# ASCII.net
KiCad netlist of a schematic drawn in Altium Designer
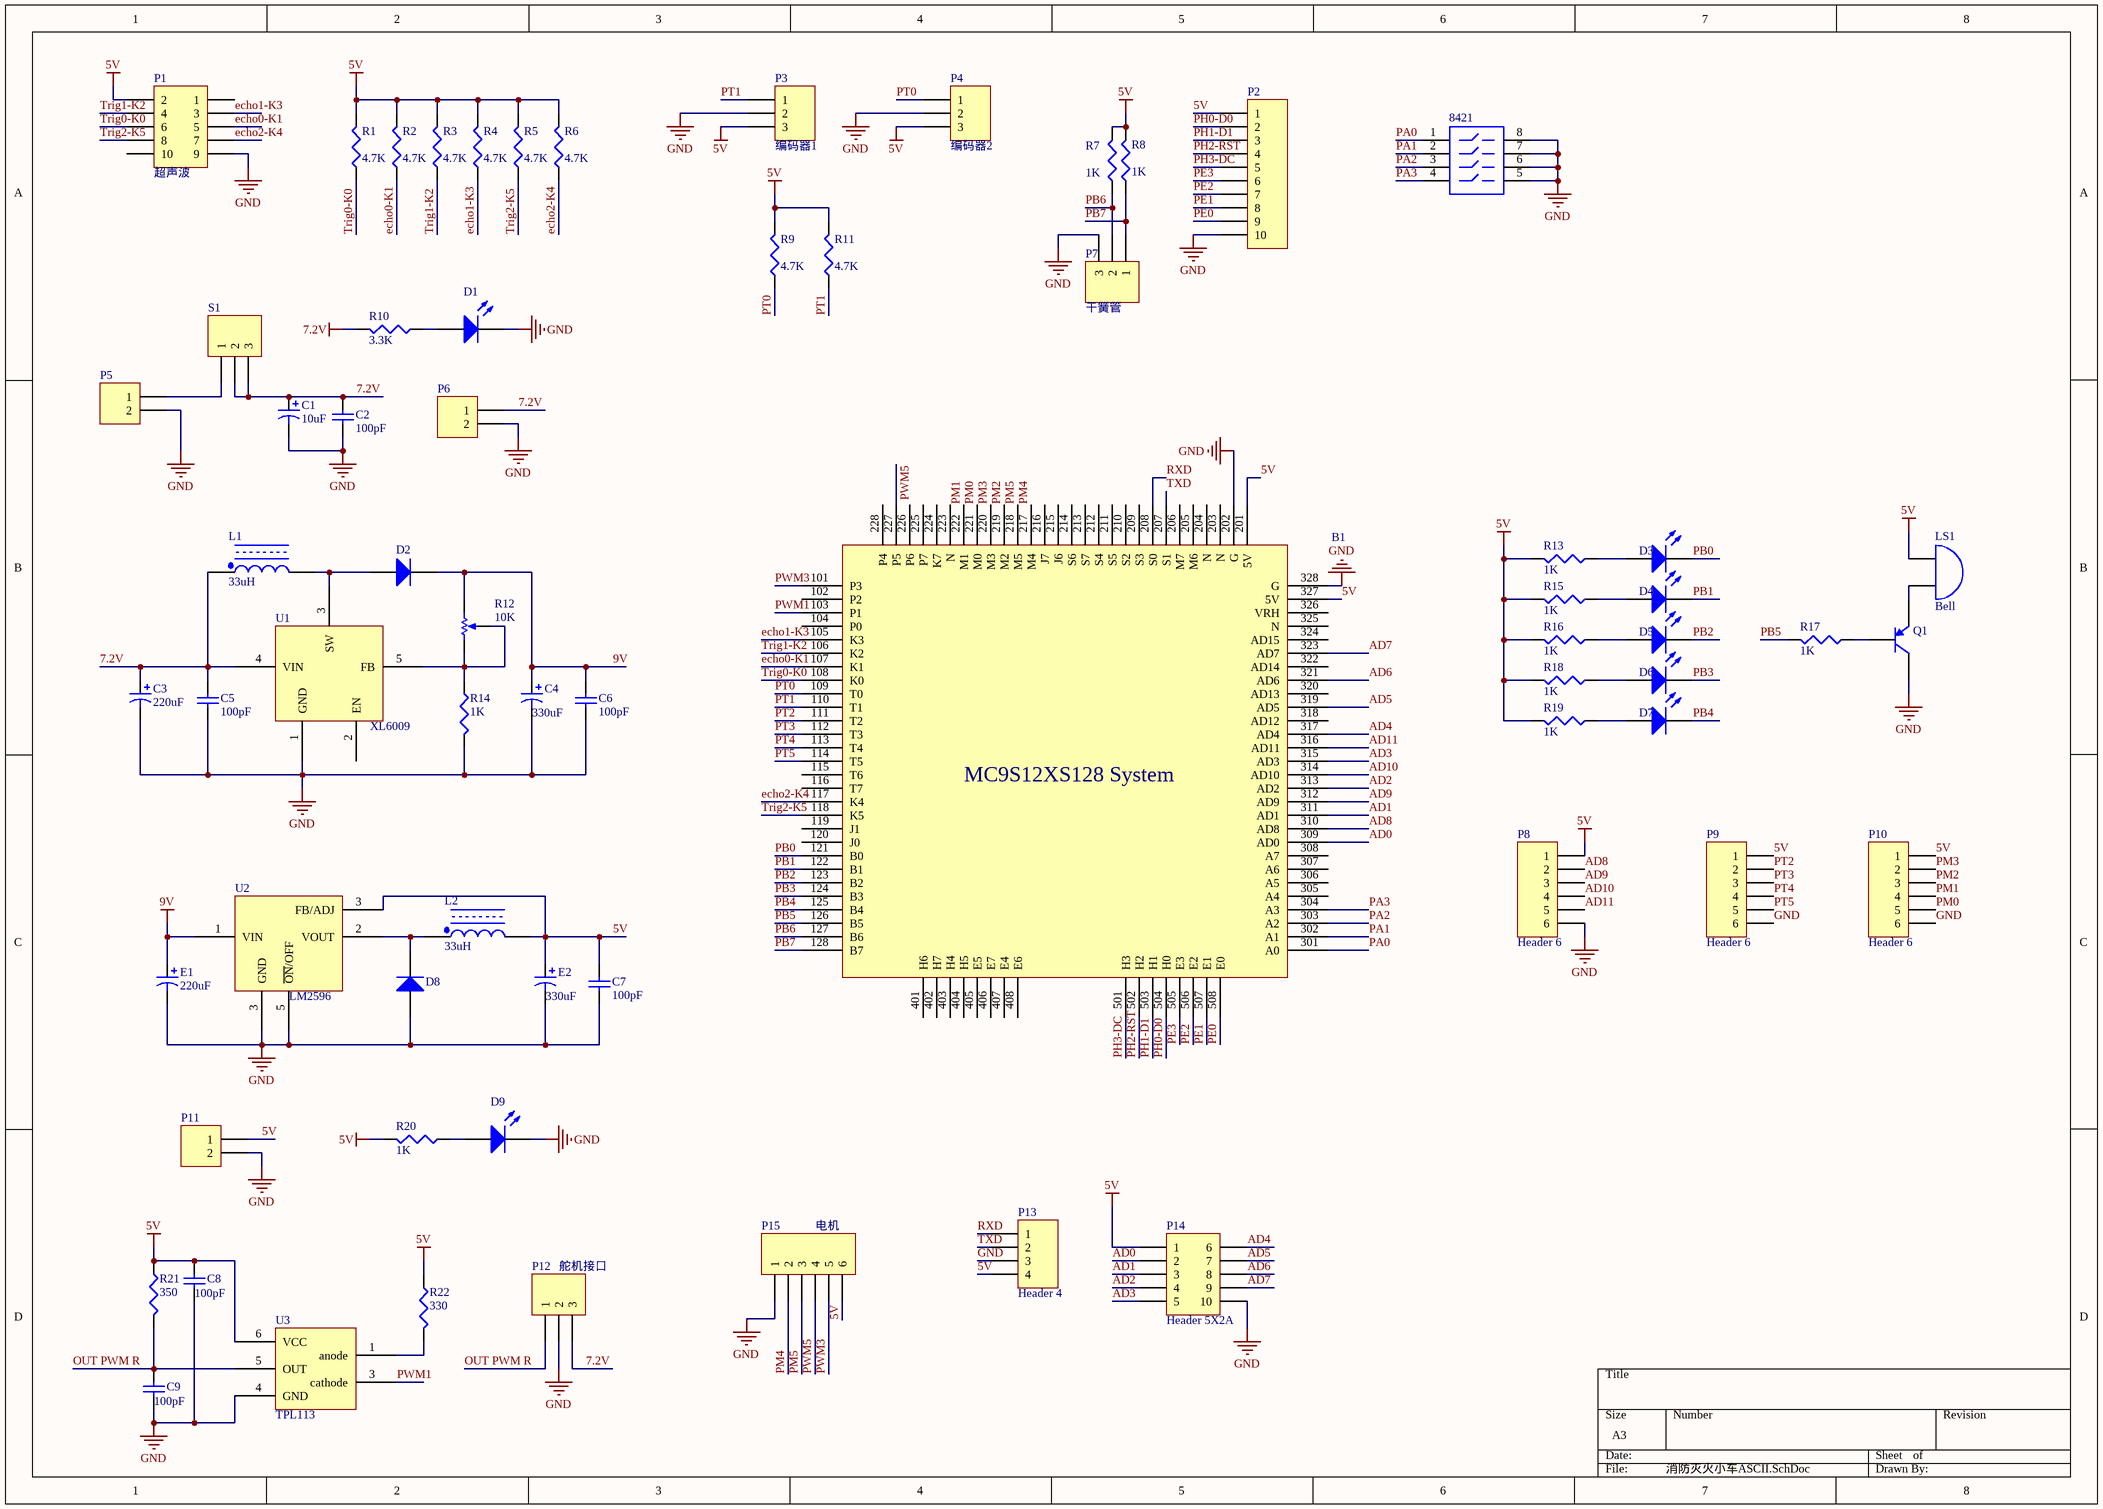
[diagram p0: 消防灭火小车ASCII.SchDoc]

(export (version "E")
  (design (tool "Eeschema 10.0.6"))
  (components
    (comp (ref "8421")
      (value "SW-DIP4")
      (footprint "DIP-8")
      (description "DIP Switch")
      (fields (field (name "PUBLISHER") "Altium Limited"))
      (libsource (lib "Miscellaneous Devices") (part "SW-DIP4"))
    )
    (comp (ref "B1")
      (value "Component_1")
      (footprint "XS128")
      (libsource (lib "XS128P112") (part "Component_1"))
    )
    (comp (ref "C1")
      (value "10uF")
      (footprint "C0805")
      (description "Polarized Capacitor (Surface Mount)")
      (fields (field (name "Comment") "Cap Pol3") (field (name "PUBLISHER") "Altium Limited"))
      (libsource (lib "Miscellaneous Devices") (part "Cap Pol3"))
    )
    (comp (ref "C2")
      (value "100pF")
      (footprint "C1206")
      (description "Capacitor (Semiconductor SIM Model)")
      (fields (field (name "Comment") "Cap Semi") (field (name "PUBLISHER") "Altium Limited"))
      (libsource (lib "Miscellaneous Devices") (part "Cap Semi"))
    )
    (comp (ref "C3")
      (value "220uF")
      (footprint "C0805")
      (description "Polarized Capacitor (Surface Mount)")
      (fields (field (name "Comment") "Cap Pol3") (field (name "PUBLISHER") "Altium Limited"))
      (libsource (lib "Miscellaneous Devices") (part "Cap Pol3"))
    )
    (comp (ref "C4")
      (value "330uF")
      (footprint "C0805")
      (description "Polarized Capacitor (Surface Mount)")
      (fields (field (name "Comment") "Cap Pol3") (field (name "PUBLISHER") "Altium Limited"))
      (libsource (lib "Miscellaneous Devices") (part "Cap Pol3"))
    )
    (comp (ref "C5")
      (value "100pF")
      (footprint "C1206")
      (description "Capacitor (Semiconductor SIM Model)")
      (fields (field (name "Comment") "Cap Semi") (field (name "PUBLISHER") "Altium Limited"))
      (libsource (lib "Miscellaneous Devices") (part "Cap Semi"))
    )
    (comp (ref "C6")
      (value "100pF")
      (footprint "C1206")
      (description "Capacitor (Semiconductor SIM Model)")
      (fields (field (name "Comment") "Cap Semi") (field (name "PUBLISHER") "Altium Limited"))
      (libsource (lib "Miscellaneous Devices") (part "Cap Semi"))
    )
    (comp (ref "C7")
      (value "100pF")
      (footprint "C1206")
      (description "Capacitor (Semiconductor SIM Model)")
      (fields (field (name "Comment") "Cap Semi") (field (name "PUBLISHER") "Altium Limited"))
      (libsource (lib "Miscellaneous Devices") (part "Cap Semi"))
    )
    (comp (ref "C8")
      (value "100pF")
      (footprint "C1206")
      (description "Capacitor (Semiconductor SIM Model)")
      (fields (field (name "Comment") "Cap Semi") (field (name "PUBLISHER") "Altium Limited"))
      (libsource (lib "Miscellaneous Devices") (part "Cap Semi"))
    )
    (comp (ref "C9")
      (value "100pF")
      (footprint "C1206")
      (description "Capacitor (Semiconductor SIM Model)")
      (fields (field (name "Comment") "Cap Semi") (field (name "PUBLISHER") "Altium Limited"))
      (libsource (lib "Miscellaneous Devices") (part "Cap Semi"))
    )
    (comp (ref "D1")
      (value "LED2")
      (footprint "3.2X1.6X1.1")
      (description "Typical RED, GREEN, YELLOW, AMBER GaAs LED")
      (fields (field (name "PUBLISHER") "Altium Limited"))
      (libsource (lib "Miscellaneous Devices") (part "LED2"))
    )
    (comp (ref "D2")
      (value "Diode")
      (footprint "SMC")
      (description "Default Diode")
      (fields (field (name "PUBLISHER") "Altium Limited"))
      (libsource (lib "Miscellaneous Devices") (part "Diode"))
    )
    (comp (ref "D3")
      (value "LED2")
      (footprint "3.2X1.6X1.1")
      (description "Typical RED, GREEN, YELLOW, AMBER GaAs LED")
      (fields (field (name "PUBLISHER") "Altium Limited"))
      (libsource (lib "Miscellaneous Devices") (part "LED2"))
    )
    (comp (ref "D4")
      (value "LED2")
      (footprint "3.2X1.6X1.1")
      (description "Typical RED, GREEN, YELLOW, AMBER GaAs LED")
      (fields (field (name "PUBLISHER") "Altium Limited"))
      (libsource (lib "Miscellaneous Devices") (part "LED2"))
    )
    (comp (ref "D5")
      (value "LED2")
      (footprint "3.2X1.6X1.1")
      (description "Typical RED, GREEN, YELLOW, AMBER GaAs LED")
      (fields (field (name "PUBLISHER") "Altium Limited"))
      (libsource (lib "Miscellaneous Devices") (part "LED2"))
    )
    (comp (ref "D6")
      (value "LED2")
      (footprint "3.2X1.6X1.1")
      (description "Typical RED, GREEN, YELLOW, AMBER GaAs LED")
      (fields (field (name "PUBLISHER") "Altium Limited"))
      (libsource (lib "Miscellaneous Devices") (part "LED2"))
    )
    (comp (ref "D7")
      (value "LED2")
      (footprint "3.2X1.6X1.1")
      (description "Typical RED, GREEN, YELLOW, AMBER GaAs LED")
      (fields (field (name "PUBLISHER") "Altium Limited"))
      (libsource (lib "Miscellaneous Devices") (part "LED2"))
    )
    (comp (ref "D8")
      (value "Diode")
      (footprint "SMC")
      (description "Default Diode")
      (fields (field (name "PUBLISHER") "Altium Limited"))
      (libsource (lib "Miscellaneous Devices") (part "Diode"))
    )
    (comp (ref "D9")
      (value "LED2")
      (footprint "3.2X1.6X1.1")
      (description "Typical RED, GREEN, YELLOW, AMBER GaAs LED")
      (fields (field (name "PUBLISHER") "Altium Limited"))
      (libsource (lib "Miscellaneous Devices") (part "LED2"))
    )
    (comp (ref "E1")
      (value "220uF")
      (footprint "C0805")
      (description "Polarized Capacitor (Surface Mount)")
      (fields (field (name "Comment") "Cap Pol3") (field (name "PUBLISHER") "Altium Limited"))
      (libsource (lib "Miscellaneous Devices") (part "Cap Pol3"))
    )
    (comp (ref "E2")
      (value "330uF")
      (footprint "C0805")
      (description "Polarized Capacitor (Surface Mount)")
      (fields (field (name "Comment") "Cap Pol3") (field (name "PUBLISHER") "Altium Limited"))
      (libsource (lib "Miscellaneous Devices") (part "Cap Pol3"))
    )
    (comp (ref "L1")
      (value "33uH")
      (footprint "425")
      (description "Isolated Inductor")
      (fields (field (name "Comment") "Inductor Isolated") (field (name "PUBLISHER") "Altium Limited"))
      (libsource (lib "Miscellaneous Devices") (part "Inductor Isolated"))
    )
    (comp (ref "L2")
      (value "33uH")
      (footprint "425")
      (description "Isolated Inductor")
      (fields (field (name "Comment") "Inductor Isolated") (field (name "PUBLISHER") "Altium Limited"))
      (libsource (lib "Miscellaneous Devices") (part "Inductor Isolated"))
    )
    (comp (ref "LS1")
      (value "Bell")
      (footprint "PIN2")
      (description "Electrical Bell")
      (fields (field (name "PUBLISHER") "Altium Limited"))
      (libsource (lib "Miscellaneous Devices") (part "Bell"))
    )
    (comp (ref "P1")
      (value "超声波")
      (footprint "MHDR2X5")
      (description "Header, 5-Pin, Dual row")
      (fields (field (name "PUBLISHER") "Altium Limited"))
      (libsource (lib "Miscellaneous Connectors") (part "MHDR2X5"))
    )
    (comp (ref "P2")
      (value "Header 10")
      (footprint "HDR1X10")
      (description "Header, 10-Pin")
      (fields (field (name "PUBLISHER") "Altium Limited"))
      (libsource (lib "Miscellaneous Connectors") (part "Header 10"))
    )
    (comp (ref "P3")
      (value "编码器1")
      (footprint "HDR1X3")
      (description "Header, 3-Pin")
      (fields (field (name "PUBLISHER") "Altium Limited"))
      (libsource (lib "") (part "Header 3_2"))
    )
    (comp (ref "P4")
      (value "编码器2")
      (footprint "HDR1X3")
      (description "Header, 3-Pin")
      (fields (field (name "PUBLISHER") "Altium Limited"))
      (libsource (lib "") (part "Header 3_2"))
    )
    (comp (ref "P5")
      (value "Header 2")
      (footprint "HDR1X2")
      (description "Header, 2-Pin")
      (fields (field (name "PUBLISHER") "Altium Limited"))
      (libsource (lib "Miscellaneous Connectors") (part "Header 2"))
    )
    (comp (ref "P6")
      (value "Header 2")
      (footprint "HDR1X2")
      (description "Header, 2-Pin")
      (fields (field (name "PUBLISHER") "Altium Limited"))
      (libsource (lib "Miscellaneous Connectors") (part "Header 2"))
    )
    (comp (ref "P7")
      (value "干簧管")
      (footprint "HDR1X3")
      (description "Header, 3-Pin")
      (fields (field (name "PUBLISHER") "Altium Limited"))
      (libsource (lib "Miscellaneous Connectors") (part "Header 3"))
    )
    (comp (ref "P8")
      (value "Header 6")
      (footprint "HDR1X6")
      (description "Header, 6-Pin")
      (fields (field (name "PUBLISHER") "Altium Limited"))
      (libsource (lib "") (part "Header 6_1"))
    )
    (comp (ref "P9")
      (value "Header 6")
      (footprint "HDR1X6")
      (description "Header, 6-Pin")
      (fields (field (name "PUBLISHER") "Altium Limited"))
      (libsource (lib "") (part "Header 6_1"))
    )
    (comp (ref "P10")
      (value "Header 6")
      (footprint "HDR1X6")
      (description "Header, 6-Pin")
      (fields (field (name "PUBLISHER") "Altium Limited"))
      (libsource (lib "") (part "Header 6_1"))
    )
    (comp (ref "P11")
      (value "Header 2")
      (footprint "HDR1X2")
      (description "Header, 2-Pin")
      (fields (field (name "PUBLISHER") "Altium Limited"))
      (libsource (lib "Miscellaneous Connectors") (part "Header 2"))
    )
    (comp (ref "P12")
      (value "舵机接口")
      (footprint "HDR1X3")
      (description "Header, 3-Pin")
      (fields (field (name "PUBLISHER") "Altium Limited"))
      (libsource (lib "") (part "Header 3_1"))
    )
    (comp (ref "P13")
      (value "Header 4")
      (footprint "HDR1X4")
      (description "Header, 4-Pin")
      (fields (field (name "PUBLISHER") "Altium Limited"))
      (libsource (lib "Miscellaneous Connectors") (part "Header 4"))
    )
    (comp (ref "P14")
      (value "Header 5X2A")
      (footprint "HDR2X5_CEN")
      (description "Header, 5-Pin, Dual row")
      (fields (field (name "PUBLISHER") "Altium Limited"))
      (libsource (lib "Miscellaneous Connectors") (part "Header 5X2A"))
    )
    (comp (ref "P15")
      (value "电机")
      (footprint "HDR1X6")
      (description "Header, 6-Pin")
      (fields (field (name "PUBLISHER") "Altium Limited"))
      (libsource (lib "Miscellaneous Connectors") (part "Header 6"))
    )
    (comp (ref "Q1")
      (value "2N3906")
      (footprint "TO-92A")
      (description "PNP General Purpose Amplifier")
      (fields (field (name "PUBLISHER") "Altium Limited"))
      (libsource (lib "Miscellaneous Devices") (part "2N3906"))
    )
    (comp (ref "R1")
      (value "4.7K")
      (footprint "J1-0603")
      (description "Resistor")
      (fields (field (name "Comment") "Res3") (field (name "PUBLISHER") "Altium Limited"))
      (libsource (lib "Miscellaneous Devices") (part "Res3"))
    )
    (comp (ref "R2")
      (value "4.7K")
      (footprint "J1-0603")
      (description "Resistor")
      (fields (field (name "Comment") "Res3") (field (name "PUBLISHER") "Altium Limited"))
      (libsource (lib "Miscellaneous Devices") (part "Res3"))
    )
    (comp (ref "R3")
      (value "4.7K")
      (footprint "J1-0603")
      (description "Resistor")
      (fields (field (name "Comment") "Res3") (field (name "PUBLISHER") "Altium Limited"))
      (libsource (lib "Miscellaneous Devices") (part "Res3"))
    )
    (comp (ref "R4")
      (value "4.7K")
      (footprint "J1-0603")
      (description "Resistor")
      (fields (field (name "Comment") "Res3") (field (name "PUBLISHER") "Altium Limited"))
      (libsource (lib "Miscellaneous Devices") (part "Res3"))
    )
    (comp (ref "R5")
      (value "4.7K")
      (footprint "J1-0603")
      (description "Resistor")
      (fields (field (name "Comment") "Res3") (field (name "PUBLISHER") "Altium Limited"))
      (libsource (lib "Miscellaneous Devices") (part "Res3"))
    )
    (comp (ref "R6")
      (value "4.7K")
      (footprint "J1-0603")
      (description "Resistor")
      (fields (field (name "Comment") "Res3") (field (name "PUBLISHER") "Altium Limited"))
      (libsource (lib "Miscellaneous Devices") (part "Res3"))
    )
    (comp (ref "R7")
      (value "1K")
      (footprint "J1-0603")
      (description "Resistor")
      (fields (field (name "Comment") "Res3") (field (name "PUBLISHER") "Altium Limited"))
      (libsource (lib "Miscellaneous Devices") (part "Res3"))
    )
    (comp (ref "R8")
      (value "1K")
      (footprint "J1-0603")
      (description "Resistor")
      (fields (field (name "Comment") "Res3") (field (name "PUBLISHER") "Altium Limited"))
      (libsource (lib "Miscellaneous Devices") (part "Res3"))
    )
    (comp (ref "R9")
      (value "4.7K")
      (footprint "J1-0603")
      (description "Resistor")
      (fields (field (name "Comment") "Res3") (field (name "PUBLISHER") "Altium Limited"))
      (libsource (lib "Miscellaneous Devices") (part "Res3"))
    )
    (comp (ref "R10")
      (value "3.3K")
      (footprint "J1-0603")
      (description "Resistor")
      (fields (field (name "Comment") "Res3") (field (name "PUBLISHER") "Altium Limited"))
      (libsource (lib "Miscellaneous Devices") (part "Res3"))
    )
    (comp (ref "R11")
      (value "4.7K")
      (footprint "J1-0603")
      (description "Resistor")
      (fields (field (name "Comment") "Res3") (field (name "PUBLISHER") "Altium Limited"))
      (libsource (lib "Miscellaneous Devices") (part "Res3"))
    )
    (comp (ref "R12")
      (value "10K")
      (footprint "VR5")
      (description "Potentiometer")
      (fields (field (name "Comment") "RPot") (field (name "PUBLISHER") "Altium Limited"))
      (libsource (lib "Miscellaneous Devices") (part "RPot"))
    )
    (comp (ref "R13")
      (value "1K")
      (footprint "J1-0603")
      (description "Resistor")
      (fields (field (name "Comment") "Res3") (field (name "PUBLISHER") "Altium Limited"))
      (libsource (lib "Miscellaneous Devices") (part "Res3"))
    )
    (comp (ref "R14")
      (value "1K")
      (footprint "J1-0603")
      (description "Resistor")
      (fields (field (name "Comment") "Res3") (field (name "PUBLISHER") "Altium Limited"))
      (libsource (lib "Miscellaneous Devices") (part "Res3"))
    )
    (comp (ref "R15")
      (value "1K")
      (footprint "J1-0603")
      (description "Resistor")
      (fields (field (name "Comment") "Res3") (field (name "PUBLISHER") "Altium Limited"))
      (libsource (lib "Miscellaneous Devices") (part "Res3"))
    )
    (comp (ref "R16")
      (value "1K")
      (footprint "J1-0603")
      (description "Resistor")
      (fields (field (name "Comment") "Res3") (field (name "PUBLISHER") "Altium Limited"))
      (libsource (lib "Miscellaneous Devices") (part "Res3"))
    )
    (comp (ref "R17")
      (value "1K")
      (footprint "J1-0603")
      (description "Resistor")
      (fields (field (name "Comment") "Res3") (field (name "PUBLISHER") "Altium Limited"))
      (libsource (lib "Miscellaneous Devices") (part "Res3"))
    )
    (comp (ref "R18")
      (value "1K")
      (footprint "J1-0603")
      (description "Resistor")
      (fields (field (name "Comment") "Res3") (field (name "PUBLISHER") "Altium Limited"))
      (libsource (lib "Miscellaneous Devices") (part "Res3"))
    )
    (comp (ref "R19")
      (value "1K")
      (footprint "J1-0603")
      (description "Resistor")
      (fields (field (name "Comment") "Res3") (field (name "PUBLISHER") "Altium Limited"))
      (libsource (lib "Miscellaneous Devices") (part "Res3"))
    )
    (comp (ref "R20")
      (value "1K")
      (footprint "J1-0603")
      (description "Resistor")
      (fields (field (name "Comment") "Res3") (field (name "PUBLISHER") "Altium Limited"))
      (libsource (lib "Miscellaneous Devices") (part "Res3"))
    )
    (comp (ref "R21")
      (value "350")
      (footprint "J1-0603")
      (description "Resistor")
      (fields (field (name "Comment") "Res3") (field (name "PUBLISHER") "Altium Limited"))
      (libsource (lib "Miscellaneous Devices") (part "Res3"))
    )
    (comp (ref "R22")
      (value "330")
      (footprint "J1-0603")
      (description "Resistor")
      (fields (field (name "Comment") "Res3") (field (name "PUBLISHER") "Altium Limited"))
      (libsource (lib "Miscellaneous Devices") (part "Res3"))
    )
    (comp (ref "S1")
      (value "Header 3")
      (footprint "HDR1X3")
      (description "Header, 3-Pin")
      (fields (field (name "PUBLISHER") "Altium Limited"))
      (libsource (lib "") (part "Header 3_1"))
    )
    (comp (ref "U1")
      (value "XL6009")
      (footprint "XL6009E1")
      (libsource (lib "XL6009E1") (part "Component_1"))
    )
    (comp (ref "U2") (value "LM2596") (footprint "LM2596") (libsource (lib "LM2596") (part "Component_1")))
    (comp (ref "U3") (value "TPL113") (footprint "TLP113") (libsource (lib "TLP113") (part "Component_1")))
  )
  (nets
    (net (code "1") (name "/AD0") (class "Default")
      (node (ref "B1") (pin "309") (pinfunction "AD0_309") (pintype "passive"))
      (node (ref "P14") (pin "2") (pinfunction "2_2") (pintype "passive"))
    )
    (net (code "2") (name "/AD1") (class "Default")
      (node (ref "B1") (pin "311") (pinfunction "AD1_311") (pintype "passive"))
      (node (ref "P14") (pin "3") (pinfunction "3_3") (pintype "passive"))
    )
    (net (code "3") (name "/AD2") (class "Default")
      (node (ref "B1") (pin "313") (pinfunction "AD2_313") (pintype "passive"))
      (node (ref "P14") (pin "4") (pinfunction "4_4") (pintype "passive"))
    )
    (net (code "4") (name "/AD3") (class "Default")
      (node (ref "B1") (pin "315") (pinfunction "AD3_315") (pintype "passive"))
      (node (ref "P14") (pin "5") (pinfunction "5_5") (pintype "passive"))
    )
    (net (code "5") (name "/AD4") (class "Default")
      (node (ref "B1") (pin "317") (pinfunction "AD4_317") (pintype "passive"))
      (node (ref "P14") (pin "6") (pinfunction "6_6") (pintype "passive"))
    )
    (net (code "6") (name "/AD5") (class "Default")
      (node (ref "B1") (pin "319") (pinfunction "AD5_319") (pintype "passive"))
      (node (ref "P14") (pin "7") (pinfunction "7_7") (pintype "passive"))
    )
    (net (code "7") (name "/AD6") (class "Default")
      (node (ref "B1") (pin "321") (pinfunction "AD6_321") (pintype "passive"))
      (node (ref "P14") (pin "8") (pinfunction "8_8") (pintype "passive"))
    )
    (net (code "8") (name "/AD7") (class "Default")
      (node (ref "B1") (pin "323") (pinfunction "AD7_323") (pintype "passive"))
      (node (ref "P14") (pin "9") (pinfunction "9_9") (pintype "passive"))
    )
    (net (code "9") (name "/AD8") (class "Default")
      (node (ref "B1") (pin "310") (pinfunction "AD8_310") (pintype "passive"))
      (node (ref "P8") (pin "2") (pinfunction "2_2") (pintype "passive"))
    )
    (net (code "10") (name "/AD9") (class "Default")
      (node (ref "B1") (pin "312") (pinfunction "AD9_312") (pintype "passive"))
      (node (ref "P8") (pin "3") (pinfunction "3_3") (pintype "passive"))
    )
    (net (code "11") (name "/AD10") (class "Default")
      (node (ref "B1") (pin "314") (pinfunction "AD10_314") (pintype "passive"))
      (node (ref "P8") (pin "4") (pinfunction "4_4") (pintype "passive"))
    )
    (net (code "12") (name "/AD11") (class "Default")
      (node (ref "B1") (pin "316") (pinfunction "AD11_316") (pintype "passive"))
      (node (ref "P8") (pin "5") (pinfunction "5_5") (pintype "passive"))
    )
    (net (code "13") (name "/OUT PWM R") (class "Default")
      (node (ref "C9") (pin "2") (pinfunction "2_2") (pintype "passive"))
      (node (ref "P12") (pin "1") (pinfunction "1_1") (pintype "passive"))
      (node (ref "R21") (pin "2") (pinfunction "2_2") (pintype "passive"))
      (node (ref "U3") (pin "5") (pinfunction "OUT_5") (pintype "passive"))
    )
    (net (code "14") (name "/PA0") (class "Default")
      (node (ref "8421") (pin "1") (pinfunction "1_1") (pintype "passive"))
      (node (ref "B1") (pin "301") (pinfunction "A0_301") (pintype "passive"))
    )
    (net (code "15") (name "/PA1") (class "Default")
      (node (ref "8421") (pin "2") (pinfunction "2_2") (pintype "passive"))
      (node (ref "B1") (pin "302") (pinfunction "A1_302") (pintype "passive"))
    )
    (net (code "16") (name "/PA2") (class "Default")
      (node (ref "8421") (pin "3") (pinfunction "3_3") (pintype "passive"))
      (node (ref "B1") (pin "303") (pinfunction "A2_303") (pintype "passive"))
    )
    (net (code "17") (name "/PA3") (class "Default")
      (node (ref "8421") (pin "4") (pinfunction "4_4") (pintype "passive"))
      (node (ref "B1") (pin "304") (pinfunction "A3_304") (pintype "passive"))
    )
    (net (code "18") (name "/PB0") (class "Default")
      (node (ref "B1") (pin "121") (pinfunction "B0_121") (pintype "passive"))
      (node (ref "D3") (pin "2") (pinfunction "K_2") (pintype "passive"))
    )
    (net (code "19") (name "/PB1") (class "Default")
      (node (ref "B1") (pin "122") (pinfunction "B1_122") (pintype "passive"))
      (node (ref "D4") (pin "2") (pinfunction "K_2") (pintype "passive"))
    )
    (net (code "20") (name "/PB2") (class "Default")
      (node (ref "B1") (pin "123") (pinfunction "B2_123") (pintype "passive"))
      (node (ref "D5") (pin "2") (pinfunction "K_2") (pintype "passive"))
    )
    (net (code "21") (name "/PB3") (class "Default")
      (node (ref "B1") (pin "124") (pinfunction "B3_124") (pintype "passive"))
      (node (ref "D6") (pin "2") (pinfunction "K_2") (pintype "passive"))
    )
    (net (code "22") (name "/PB4") (class "Default")
      (node (ref "B1") (pin "125") (pinfunction "B4_125") (pintype "passive"))
      (node (ref "D7") (pin "2") (pinfunction "K_2") (pintype "passive"))
    )
    (net (code "23") (name "/PB5") (class "Default")
      (node (ref "B1") (pin "126") (pinfunction "B5_126") (pintype "passive"))
      (node (ref "R17") (pin "2") (pinfunction "2_2") (pintype "passive"))
    )
    (net (code "24") (name "/PB6") (class "Default")
      (node (ref "B1") (pin "127") (pinfunction "B6_127") (pintype "passive"))
      (node (ref "P7") (pin "2") (pinfunction "2_2") (pintype "passive"))
      (node (ref "R7") (pin "1") (pinfunction "1_1") (pintype "passive"))
    )
    (net (code "25") (name "/PB7") (class "Default")
      (node (ref "B1") (pin "128") (pinfunction "B7_128") (pintype "passive"))
      (node (ref "P7") (pin "1") (pinfunction "1_1") (pintype "passive"))
      (node (ref "R8") (pin "1") (pinfunction "1_1") (pintype "passive"))
    )
    (net (code "26") (name "/PE0") (class "Default")
      (node (ref "B1") (pin "508") (pinfunction "E0_508") (pintype "passive"))
      (node (ref "P2") (pin "9") (pinfunction "9_9") (pintype "passive"))
    )
    (net (code "27") (name "/PE1") (class "Default")
      (node (ref "B1") (pin "507") (pinfunction "E1_507") (pintype "passive"))
      (node (ref "P2") (pin "8") (pinfunction "8_8") (pintype "passive"))
    )
    (net (code "28") (name "/PE2") (class "Default")
      (node (ref "B1") (pin "506") (pinfunction "E2_506") (pintype "passive"))
      (node (ref "P2") (pin "7") (pinfunction "7_7") (pintype "passive"))
    )
    (net (code "29") (name "/PE3") (class "Default")
      (node (ref "B1") (pin "505") (pinfunction "E3_505") (pintype "passive"))
      (node (ref "P2") (pin "6") (pinfunction "6_6") (pintype "passive"))
    )
    (net (code "30") (name "/PH0-D0") (class "Default")
      (node (ref "B1") (pin "504") (pinfunction "H0_504") (pintype "passive"))
      (node (ref "P2") (pin "2") (pinfunction "2_2") (pintype "passive"))
    )
    (net (code "31") (name "/PH1-D1") (class "Default")
      (node (ref "B1") (pin "503") (pinfunction "H1_503") (pintype "passive"))
      (node (ref "P2") (pin "3") (pinfunction "3_3") (pintype "passive"))
    )
    (net (code "32") (name "/PH2-RST") (class "Default")
      (node (ref "B1") (pin "502") (pinfunction "H2_502") (pintype "passive"))
      (node (ref "P2") (pin "4") (pinfunction "4_4") (pintype "passive"))
    )
    (net (code "33") (name "/PH3-DC") (class "Default")
      (node (ref "B1") (pin "501") (pinfunction "H3_501") (pintype "passive"))
      (node (ref "P2") (pin "5") (pinfunction "5_5") (pintype "passive"))
    )
    (net (code "34") (name "/PM0") (class "Default")
      (node (ref "B1") (pin "221") (pinfunction "M0_221") (pintype "passive"))
      (node (ref "P10") (pin "5") (pinfunction "5_5") (pintype "passive"))
    )
    (net (code "35") (name "/PM1") (class "Default")
      (node (ref "B1") (pin "222") (pinfunction "M1_222") (pintype "passive"))
      (node (ref "P10") (pin "4") (pinfunction "4_4") (pintype "passive"))
    )
    (net (code "36") (name "/PM2") (class "Default")
      (node (ref "B1") (pin "219") (pinfunction "M2_219") (pintype "passive"))
      (node (ref "P10") (pin "3") (pinfunction "3_3") (pintype "passive"))
    )
    (net (code "37") (name "/PM3") (class "Default")
      (node (ref "B1") (pin "220") (pinfunction "M3_220") (pintype "passive"))
      (node (ref "P10") (pin "2") (pinfunction "2_2") (pintype "passive"))
    )
    (net (code "38") (name "/PM4") (class "Default")
      (node (ref "B1") (pin "217") (pinfunction "M4_217") (pintype "passive"))
      (node (ref "P15") (pin "2") (pinfunction "2_2") (pintype "passive"))
    )
    (net (code "39") (name "/PM5") (class "Default")
      (node (ref "B1") (pin "218") (pinfunction "M5_218") (pintype "passive"))
      (node (ref "P15") (pin "3") (pinfunction "3_3") (pintype "passive"))
    )
    (net (code "40") (name "/PT0") (class "Default")
      (node (ref "B1") (pin "109") (pinfunction "T0_109") (pintype "passive"))
      (node (ref "P4") (pin "1") (pinfunction "1_1") (pintype "passive"))
      (node (ref "R9") (pin "1") (pinfunction "1_1") (pintype "passive"))
    )
    (net (code "41") (name "/PT1") (class "Default")
      (node (ref "B1") (pin "110") (pinfunction "T1_110") (pintype "passive"))
      (node (ref "P3") (pin "1") (pinfunction "1_1") (pintype "passive"))
      (node (ref "R11") (pin "1") (pinfunction "1_1") (pintype "passive"))
    )
    (net (code "42") (name "/PT2") (class "Default")
      (node (ref "B1") (pin "111") (pinfunction "T2_111") (pintype "passive"))
      (node (ref "P9") (pin "2") (pinfunction "2_2") (pintype "passive"))
    )
    (net (code "43") (name "/PT3") (class "Default")
      (node (ref "B1") (pin "112") (pinfunction "T3_112") (pintype "passive"))
      (node (ref "P9") (pin "3") (pinfunction "3_3") (pintype "passive"))
    )
    (net (code "44") (name "/PT4") (class "Default")
      (node (ref "B1") (pin "113") (pinfunction "T4_113") (pintype "passive"))
      (node (ref "P9") (pin "4") (pinfunction "4_4") (pintype "passive"))
    )
    (net (code "45") (name "/PT5") (class "Default")
      (node (ref "B1") (pin "114") (pinfunction "T5_114") (pintype "passive"))
      (node (ref "P9") (pin "5") (pinfunction "5_5") (pintype "passive"))
    )
    (net (code "46") (name "/PWM1") (class "Default")
      (node (ref "B1") (pin "103") (pinfunction "P1_103") (pintype "passive"))
      (node (ref "U3") (pin "3") (pinfunction "cathode_3") (pintype "passive"))
    )
    (net (code "47") (name "/PWM3") (class "Default")
      (node (ref "B1") (pin "101") (pinfunction "P3_101") (pintype "passive"))
      (node (ref "P15") (pin "5") (pinfunction "5_5") (pintype "passive"))
    )
    (net (code "48") (name "/PWM5") (class "Default")
      (node (ref "B1") (pin "227") (pinfunction "P5_227") (pintype "passive"))
      (node (ref "P15") (pin "4") (pinfunction "4_4") (pintype "passive"))
    )
    (net (code "49") (name "/RXD") (class "Default")
      (node (ref "B1") (pin "208") (pinfunction "S0_208") (pintype "passive"))
      (node (ref "P13") (pin "1") (pinfunction "1_1") (pintype "passive"))
    )
    (net (code "50") (name "/TXD") (class "Default")
      (node (ref "B1") (pin "207") (pinfunction "S1_207") (pintype "passive"))
      (node (ref "P13") (pin "2") (pinfunction "2_2") (pintype "passive"))
    )
    (net (code "51") (name "/Trig0-K0") (class "Default")
      (node (ref "B1") (pin "108") (pinfunction "K0_108") (pintype "passive"))
      (node (ref "P1") (pin "6") (pinfunction "6_6") (pintype "passive"))
      (node (ref "R1") (pin "1") (pinfunction "1_1") (pintype "passive"))
    )
    (net (code "52") (name "/Trig1-K2") (class "Default")
      (node (ref "B1") (pin "106") (pinfunction "K2_106") (pintype "passive"))
      (node (ref "P1") (pin "4") (pinfunction "4_4") (pintype "passive"))
      (node (ref "R3") (pin "1") (pinfunction "1_1") (pintype "passive"))
    )
    (net (code "53") (name "/Trig2-K5") (class "Default")
      (node (ref "B1") (pin "118") (pinfunction "K5_118") (pintype "passive"))
      (node (ref "P1") (pin "8") (pinfunction "8_8") (pintype "passive"))
      (node (ref "R5") (pin "1") (pinfunction "1_1") (pintype "passive"))
    )
    (net (code "54") (name "/echo0-K1") (class "Default")
      (node (ref "B1") (pin "107") (pinfunction "K1_107") (pintype "passive"))
      (node (ref "P1") (pin "5") (pinfunction "5_5") (pintype "passive"))
      (node (ref "R2") (pin "1") (pinfunction "1_1") (pintype "passive"))
    )
    (net (code "55") (name "/echo1-K3") (class "Default")
      (node (ref "B1") (pin "105") (pinfunction "K3_105") (pintype "passive"))
      (node (ref "P1") (pin "3") (pinfunction "3_3") (pintype "passive"))
      (node (ref "R4") (pin "1") (pinfunction "1_1") (pintype "passive"))
    )
    (net (code "56") (name "/echo2-K4") (class "Default")
      (node (ref "B1") (pin "117") (pinfunction "K4_117") (pintype "passive"))
      (node (ref "P1") (pin "7") (pinfunction "7_7") (pintype "passive"))
      (node (ref "R6") (pin "1") (pinfunction "1_1") (pintype "passive"))
    )
    (net (code "57") (name "5V") (class "Default")
      (node (ref "B1") (pin "201") (pinfunction "5V_201") (pintype "passive"))
      (node (ref "B1") (pin "327") (pinfunction "5V_327") (pintype "passive"))
      (node (ref "C7") (pin "2") (pinfunction "2_2") (pintype "passive"))
      (node (ref "C8") (pin "2") (pinfunction "2_2") (pintype "passive"))
      (node (ref "E2") (pin "1") (pinfunction "1_1") (pintype "passive"))
      (node (ref "L2") (pin "2") (pinfunction "2_2") (pintype "passive"))
      (node (ref "LS1") (pin "1") (pinfunction "A_1") (pintype "passive"))
      (node (ref "P1") (pin "2") (pinfunction "2_2") (pintype "passive"))
      (node (ref "P10") (pin "1") (pinfunction "1_1") (pintype "passive"))
      (node (ref "P11") (pin "1") (pinfunction "1_1") (pintype "passive"))
      (node (ref "P13") (pin "4") (pinfunction "4_4") (pintype "passive"))
      (node (ref "P14") (pin "1") (pinfunction "1_1") (pintype "passive"))
      (node (ref "P15") (pin "6") (pinfunction "6_6") (pintype "passive"))
      (node (ref "P2") (pin "1") (pinfunction "1_1") (pintype "passive"))
      (node (ref "P3") (pin "3") (pinfunction "3_3") (pintype "passive"))
      (node (ref "P4") (pin "3") (pinfunction "3_3") (pintype "passive"))
      (node (ref "P8") (pin "1") (pinfunction "1_1") (pintype "passive"))
      (node (ref "P9") (pin "1") (pinfunction "1_1") (pintype "passive"))
      (node (ref "R1") (pin "2") (pinfunction "2_2") (pintype "passive"))
      (node (ref "R11") (pin "2") (pinfunction "2_2") (pintype "passive"))
      (node (ref "R13") (pin "2") (pinfunction "2_2") (pintype "passive"))
      (node (ref "R15") (pin "2") (pinfunction "2_2") (pintype "passive"))
      (node (ref "R16") (pin "2") (pinfunction "2_2") (pintype "passive"))
      (node (ref "R18") (pin "2") (pinfunction "2_2") (pintype "passive"))
      (node (ref "R19") (pin "2") (pinfunction "2_2") (pintype "passive"))
      (node (ref "R2") (pin "2") (pinfunction "2_2") (pintype "passive"))
      (node (ref "R20") (pin "2") (pinfunction "2_2") (pintype "passive"))
      (node (ref "R21") (pin "1") (pinfunction "1_1") (pintype "passive"))
      (node (ref "R22") (pin "1") (pinfunction "1_1") (pintype "passive"))
      (node (ref "R3") (pin "2") (pinfunction "2_2") (pintype "passive"))
      (node (ref "R4") (pin "2") (pinfunction "2_2") (pintype "passive"))
      (node (ref "R5") (pin "2") (pinfunction "2_2") (pintype "passive"))
      (node (ref "R6") (pin "2") (pinfunction "2_2") (pintype "passive"))
      (node (ref "R7") (pin "2") (pinfunction "2_2") (pintype "passive"))
      (node (ref "R8") (pin "2") (pinfunction "2_2") (pintype "passive"))
      (node (ref "R9") (pin "2") (pinfunction "2_2") (pintype "passive"))
      (node (ref "U2") (pin "3") (pinfunction "FB/ADJ_3") (pintype "passive"))
      (node (ref "U3") (pin "6") (pinfunction "VCC_6") (pintype "passive"))
    )
    (net (code "58") (name "7.2V") (class "Default")
      (node (ref "C1") (pin "1") (pinfunction "1_1") (pintype "passive"))
      (node (ref "C2") (pin "2") (pinfunction "2_2") (pintype "passive"))
      (node (ref "C3") (pin "1") (pinfunction "1_1") (pintype "passive"))
      (node (ref "C5") (pin "2") (pinfunction "2_2") (pintype "passive"))
      (node (ref "L1") (pin "1") (pinfunction "1_1") (pintype "passive"))
      (node (ref "P12") (pin "3") (pinfunction "3_3") (pintype "passive"))
      (node (ref "P6") (pin "1") (pinfunction "1_1") (pintype "passive"))
      (node (ref "R10") (pin "2") (pinfunction "2_2") (pintype "passive"))
      (node (ref "S1") (pin "2") (pinfunction "2_2") (pintype "passive"))
      (node (ref "S1") (pin "3") (pinfunction "3_3") (pintype "passive"))
      (node (ref "U1") (pin "4") (pinfunction "VIN_4") (pintype "passive"))
    )
    (net (code "59") (name "9V") (class "Default")
      (node (ref "C4") (pin "1") (pinfunction "1_1") (pintype "passive"))
      (node (ref "C6") (pin "2") (pinfunction "2_2") (pintype "passive"))
      (node (ref "D2") (pin "2") (pinfunction "K_2") (pintype "passive"))
      (node (ref "E1") (pin "1") (pinfunction "1_1") (pintype "passive"))
      (node (ref "R12") (pin "2") (pinfunction "BOT_2") (pintype "passive"))
      (node (ref "U2") (pin "1") (pinfunction "VIN_1") (pintype "passive"))
    )
    (net (code "60") (name "GND") (class "Default")
      (node (ref "8421") (pin "5") (pinfunction "5_5") (pintype "passive"))
      (node (ref "8421") (pin "6") (pinfunction "6_6") (pintype "passive"))
      (node (ref "8421") (pin "7") (pinfunction "7_7") (pintype "passive"))
      (node (ref "8421") (pin "8") (pinfunction "8_8") (pintype "passive"))
      (node (ref "B1") (pin "202") (pinfunction "G_202") (pintype "passive"))
      (node (ref "B1") (pin "328") (pinfunction "G_328") (pintype "passive"))
      (node (ref "C1") (pin "2") (pinfunction "2_2") (pintype "passive"))
      (node (ref "C2") (pin "1") (pinfunction "1_1") (pintype "passive"))
      (node (ref "C3") (pin "2") (pinfunction "2_2") (pintype "passive"))
      (node (ref "C4") (pin "2") (pinfunction "2_2") (pintype "passive"))
      (node (ref "C5") (pin "1") (pinfunction "1_1") (pintype "passive"))
      (node (ref "C6") (pin "1") (pinfunction "1_1") (pintype "passive"))
      (node (ref "C7") (pin "1") (pinfunction "1_1") (pintype "passive"))
      (node (ref "C8") (pin "1") (pinfunction "1_1") (pintype "passive"))
      (node (ref "C9") (pin "1") (pinfunction "1_1") (pintype "passive"))
      (node (ref "D1") (pin "2") (pinfunction "K_2") (pintype "passive"))
      (node (ref "D8") (pin "1") (pinfunction "A_1") (pintype "passive"))
      (node (ref "D9") (pin "2") (pinfunction "K_2") (pintype "passive"))
      (node (ref "E1") (pin "2") (pinfunction "2_2") (pintype "passive"))
      (node (ref "E2") (pin "2") (pinfunction "2_2") (pintype "passive"))
      (node (ref "P1") (pin "9") (pinfunction "9_9") (pintype "passive"))
      (node (ref "P10") (pin "6") (pinfunction "6_6") (pintype "passive"))
      (node (ref "P11") (pin "2") (pinfunction "2_2") (pintype "passive"))
      (node (ref "P12") (pin "2") (pinfunction "2_2") (pintype "passive"))
      (node (ref "P13") (pin "3") (pinfunction "3_3") (pintype "passive"))
      (node (ref "P14") (pin "10") (pinfunction "10_10") (pintype "passive"))
      (node (ref "P15") (pin "1") (pinfunction "1_1") (pintype "passive"))
      (node (ref "P2") (pin "10") (pinfunction "10_10") (pintype "passive"))
      (node (ref "P3") (pin "2") (pinfunction "2_2") (pintype "passive"))
      (node (ref "P4") (pin "2") (pinfunction "2_2") (pintype "passive"))
      (node (ref "P5") (pin "2") (pinfunction "2_2") (pintype "passive"))
      (node (ref "P6") (pin "2") (pinfunction "2_2") (pintype "passive"))
      (node (ref "P7") (pin "3") (pinfunction "3_3") (pintype "passive"))
      (node (ref "P8") (pin "6") (pinfunction "6_6") (pintype "passive"))
      (node (ref "P9") (pin "6") (pinfunction "6_6") (pintype "passive"))
      (node (ref "Q1") (pin "3") (pinfunction "C_3") (pintype "passive"))
      (node (ref "R14") (pin "2") (pinfunction "2_2") (pintype "passive"))
      (node (ref "U1") (pin "1") (pinfunction "GND_1") (pintype "passive"))
      (node (ref "U2") (pin "3") (pinfunction "GND_3") (pintype "passive"))
      (node (ref "U2") (pin "5") (pinfunction "~{ON}/OFF_5") (pintype "passive"))
      (node (ref "U3") (pin "4") (pinfunction "GND_4") (pintype "passive"))
    )
    (net (code "61") (name "Net-(D1-A)") (class "Default")
      (node (ref "D1") (pin "1") (pinfunction "A_1") (pintype "passive"))
      (node (ref "R10") (pin "1") (pinfunction "1_1") (pintype "passive"))
    )
    (net (code "62") (name "Net-(D2-A)") (class "Default")
      (node (ref "D2") (pin "1") (pinfunction "A_1") (pintype "passive"))
      (node (ref "L1") (pin "2") (pinfunction "2_2") (pintype "passive"))
      (node (ref "U1") (pin "3") (pinfunction "SW_3") (pintype "passive"))
    )
    (net (code "63") (name "Net-(D3-A)") (class "Default")
      (node (ref "D3") (pin "1") (pinfunction "A_1") (pintype "passive"))
      (node (ref "R13") (pin "1") (pinfunction "1_1") (pintype "passive"))
    )
    (net (code "64") (name "Net-(D4-A)") (class "Default")
      (node (ref "D4") (pin "1") (pinfunction "A_1") (pintype "passive"))
      (node (ref "R15") (pin "1") (pinfunction "1_1") (pintype "passive"))
    )
    (net (code "65") (name "Net-(D5-A)") (class "Default")
      (node (ref "D5") (pin "1") (pinfunction "A_1") (pintype "passive"))
      (node (ref "R16") (pin "1") (pinfunction "1_1") (pintype "passive"))
    )
    (net (code "66") (name "Net-(D6-A)") (class "Default")
      (node (ref "D6") (pin "1") (pinfunction "A_1") (pintype "passive"))
      (node (ref "R18") (pin "1") (pinfunction "1_1") (pintype "passive"))
    )
    (net (code "67") (name "Net-(D7-A)") (class "Default")
      (node (ref "D7") (pin "1") (pinfunction "A_1") (pintype "passive"))
      (node (ref "R19") (pin "1") (pinfunction "1_1") (pintype "passive"))
    )
    (net (code "68") (name "Net-(D8-K)") (class "Default")
      (node (ref "D8") (pin "2") (pinfunction "K_2") (pintype "passive"))
      (node (ref "L2") (pin "1") (pinfunction "1_1") (pintype "passive"))
      (node (ref "U2") (pin "2") (pinfunction "VOUT_2") (pintype "passive"))
    )
    (net (code "69") (name "Net-(D9-A)") (class "Default")
      (node (ref "D9") (pin "1") (pinfunction "A_1") (pintype "passive"))
      (node (ref "R20") (pin "1") (pinfunction "1_1") (pintype "passive"))
    )
    (net (code "70") (name "Net-(LS1-B)") (class "Default")
      (node (ref "LS1") (pin "2") (pinfunction "B_2") (pintype "passive"))
      (node (ref "Q1") (pin "1") (pinfunction "E_1") (pintype "passive"))
    )
    (net (code "71") (name "Net-(P5-Pad1)") (class "Default")
      (node (ref "P5") (pin "1") (pinfunction "1_1") (pintype "passive"))
      (node (ref "S1") (pin "1") (pinfunction "1_1") (pintype "passive"))
    )
    (net (code "72") (name "Net-(Q1-B)") (class "Default")
      (node (ref "Q1") (pin "2") (pinfunction "B_2") (pintype "passive"))
      (node (ref "R17") (pin "1") (pinfunction "1_1") (pintype "passive"))
    )
    (net (code "73") (name "Net-(R12-TAP)") (class "Default")
      (node (ref "R12") (pin "1") (pinfunction "TOP_1") (pintype "passive"))
      (node (ref "R12") (pin "3") (pinfunction "TAP_3") (pintype "passive"))
      (node (ref "R14") (pin "1") (pinfunction "1_1") (pintype "passive"))
      (node (ref "U1") (pin "5") (pinfunction "FB_5") (pintype "passive"))
    )
    (net (code "74") (name "Net-(U3-anode)") (class "Default")
      (node (ref "R22") (pin "2") (pinfunction "2_2") (pintype "passive"))
      (node (ref "U3") (pin "1") (pinfunction "anode_1") (pintype "passive"))
    )
    (net (code "75") (name "unconnected-(B1-A4-Pad305)") (class "Default")
      (node (ref "B1") (pin "305") (pinfunction "A4_305") (pintype "passive"))
    )
    (net (code "76") (name "unconnected-(B1-A5-Pad306)") (class "Default")
      (node (ref "B1") (pin "306") (pinfunction "A5_306") (pintype "passive"))
    )
    (net (code "77") (name "unconnected-(B1-A6-Pad307)") (class "Default")
      (node (ref "B1") (pin "307") (pinfunction "A6_307") (pintype "passive"))
    )
    (net (code "78") (name "unconnected-(B1-A7-Pad308)") (class "Default")
      (node (ref "B1") (pin "308") (pinfunction "A7_308") (pintype "passive"))
    )
    (net (code "79") (name "unconnected-(B1-AD12-Pad318)") (class "Default")
      (node (ref "B1") (pin "318") (pinfunction "AD12_318") (pintype "passive"))
    )
    (net (code "80") (name "unconnected-(B1-AD13-Pad320)") (class "Default")
      (node (ref "B1") (pin "320") (pinfunction "AD13_320") (pintype "passive"))
    )
    (net (code "81") (name "unconnected-(B1-AD14-Pad322)") (class "Default")
      (node (ref "B1") (pin "322") (pinfunction "AD14_322") (pintype "passive"))
    )
    (net (code "82") (name "unconnected-(B1-AD15-Pad324)") (class "Default")
      (node (ref "B1") (pin "324") (pinfunction "AD15_324") (pintype "passive"))
    )
    (net (code "83") (name "unconnected-(B1-E4-Pad407)") (class "Default")
      (node (ref "B1") (pin "407") (pinfunction "E4_407") (pintype "passive"))
    )
    (net (code "84") (name "unconnected-(B1-E5-Pad405)") (class "Default")
      (node (ref "B1") (pin "405") (pinfunction "E5_405") (pintype "passive"))
    )
    (net (code "85") (name "unconnected-(B1-E6-Pad408)") (class "Default")
      (node (ref "B1") (pin "408") (pinfunction "E6_408") (pintype "passive"))
    )
    (net (code "86") (name "unconnected-(B1-E7-Pad406)") (class "Default")
      (node (ref "B1") (pin "406") (pinfunction "E7_406") (pintype "passive"))
    )
    (net (code "87") (name "unconnected-(B1-H4-Pad403)") (class "Default")
      (node (ref "B1") (pin "403") (pinfunction "H4_403") (pintype "passive"))
    )
    (net (code "88") (name "unconnected-(B1-H5-Pad404)") (class "Default")
      (node (ref "B1") (pin "404") (pinfunction "H5_404") (pintype "passive"))
    )
    (net (code "89") (name "unconnected-(B1-H6-Pad401)") (class "Default")
      (node (ref "B1") (pin "401") (pinfunction "H6_401") (pintype "passive"))
    )
    (net (code "90") (name "unconnected-(B1-H7-Pad402)") (class "Default")
      (node (ref "B1") (pin "402") (pinfunction "H7_402") (pintype "passive"))
    )
    (net (code "91") (name "unconnected-(B1-J0-Pad120)") (class "Default")
      (node (ref "B1") (pin "120") (pinfunction "J0_120") (pintype "passive"))
    )
    (net (code "92") (name "unconnected-(B1-J1-Pad119)") (class "Default")
      (node (ref "B1") (pin "119") (pinfunction "J1_119") (pintype "passive"))
    )
    (net (code "93") (name "unconnected-(B1-J6-Pad215)") (class "Default")
      (node (ref "B1") (pin "215") (pinfunction "J6_215") (pintype "passive"))
    )
    (net (code "94") (name "unconnected-(B1-J7-Pad216)") (class "Default")
      (node (ref "B1") (pin "216") (pinfunction "J7_216") (pintype "passive"))
    )
    (net (code "95") (name "unconnected-(B1-K7-Pad224)") (class "Default")
      (node (ref "B1") (pin "224") (pinfunction "K7_224") (pintype "passive"))
    )
    (net (code "96") (name "unconnected-(B1-M6-Pad205)") (class "Default")
      (node (ref "B1") (pin "205") (pinfunction "M6_205") (pintype "passive"))
    )
    (net (code "97") (name "unconnected-(B1-M7-Pad206)") (class "Default")
      (node (ref "B1") (pin "206") (pinfunction "M7_206") (pintype "passive"))
    )
    (net (code "98") (name "unconnected-(B1-N-Pad203)") (class "Default")
      (node (ref "B1") (pin "203") (pinfunction "N_203") (pintype "passive"))
    )
    (net (code "99") (name "unconnected-(B1-N-Pad204)") (class "Default")
      (node (ref "B1") (pin "204") (pinfunction "N_204") (pintype "passive"))
    )
    (net (code "100") (name "unconnected-(B1-N-Pad223)") (class "Default")
      (node (ref "B1") (pin "223") (pinfunction "N_223") (pintype "passive"))
    )
    (net (code "101") (name "unconnected-(B1-N-Pad325)") (class "Default")
      (node (ref "B1") (pin "325") (pinfunction "N_325") (pintype "passive"))
    )
    (net (code "102") (name "unconnected-(B1-P0-Pad104)") (class "Default")
      (node (ref "B1") (pin "104") (pinfunction "P0_104") (pintype "passive"))
    )
    (net (code "103") (name "unconnected-(B1-P2-Pad102)") (class "Default")
      (node (ref "B1") (pin "102") (pinfunction "P2_102") (pintype "passive"))
    )
    (net (code "104") (name "unconnected-(B1-P4-Pad228)") (class "Default")
      (node (ref "B1") (pin "228") (pinfunction "P4_228") (pintype "passive"))
    )
    (net (code "105") (name "unconnected-(B1-P6-Pad226)") (class "Default")
      (node (ref "B1") (pin "226") (pinfunction "P6_226") (pintype "passive"))
    )
    (net (code "106") (name "unconnected-(B1-P7-Pad225)") (class "Default")
      (node (ref "B1") (pin "225") (pinfunction "P7_225") (pintype "passive"))
    )
    (net (code "107") (name "unconnected-(B1-S2-Pad210)") (class "Default")
      (node (ref "B1") (pin "210") (pinfunction "S2_210") (pintype "passive"))
    )
    (net (code "108") (name "unconnected-(B1-S3-Pad209)") (class "Default")
      (node (ref "B1") (pin "209") (pinfunction "S3_209") (pintype "passive"))
    )
    (net (code "109") (name "unconnected-(B1-S4-Pad212)") (class "Default")
      (node (ref "B1") (pin "212") (pinfunction "S4_212") (pintype "passive"))
    )
    (net (code "110") (name "unconnected-(B1-S5-Pad211)") (class "Default")
      (node (ref "B1") (pin "211") (pinfunction "S5_211") (pintype "passive"))
    )
    (net (code "111") (name "unconnected-(B1-S6-Pad214)") (class "Default")
      (node (ref "B1") (pin "214") (pinfunction "S6_214") (pintype "passive"))
    )
    (net (code "112") (name "unconnected-(B1-S7-Pad213)") (class "Default")
      (node (ref "B1") (pin "213") (pinfunction "S7_213") (pintype "passive"))
    )
    (net (code "113") (name "unconnected-(B1-T6-Pad115)") (class "Default")
      (node (ref "B1") (pin "115") (pinfunction "T6_115") (pintype "passive"))
    )
    (net (code "114") (name "unconnected-(B1-T7-Pad116)") (class "Default")
      (node (ref "B1") (pin "116") (pinfunction "T7_116") (pintype "passive"))
    )
    (net (code "115") (name "unconnected-(B1-VRH-Pad326)") (class "Default")
      (node (ref "B1") (pin "326") (pinfunction "VRH_326") (pintype "passive"))
    )
    (net (code "116") (name "unconnected-(P1-Pad1)") (class "Default")
      (node (ref "P1") (pin "1") (pinfunction "1_1") (pintype "passive"))
    )
    (net (code "117") (name "unconnected-(P1-Pad10)") (class "Default")
      (node (ref "P1") (pin "10") (pinfunction "10_10") (pintype "passive"))
    )
    (net (code "118") (name "unconnected-(U1-EN-Pad2)") (class "Default")
      (node (ref "U1") (pin "2") (pinfunction "EN_2") (pintype "passive"))
    )
  )
)
